# SparkFun_Qwiic_VR_IMU_Breakout_SchDoc.net
KiCad netlist of a schematic drawn in Altium Designer
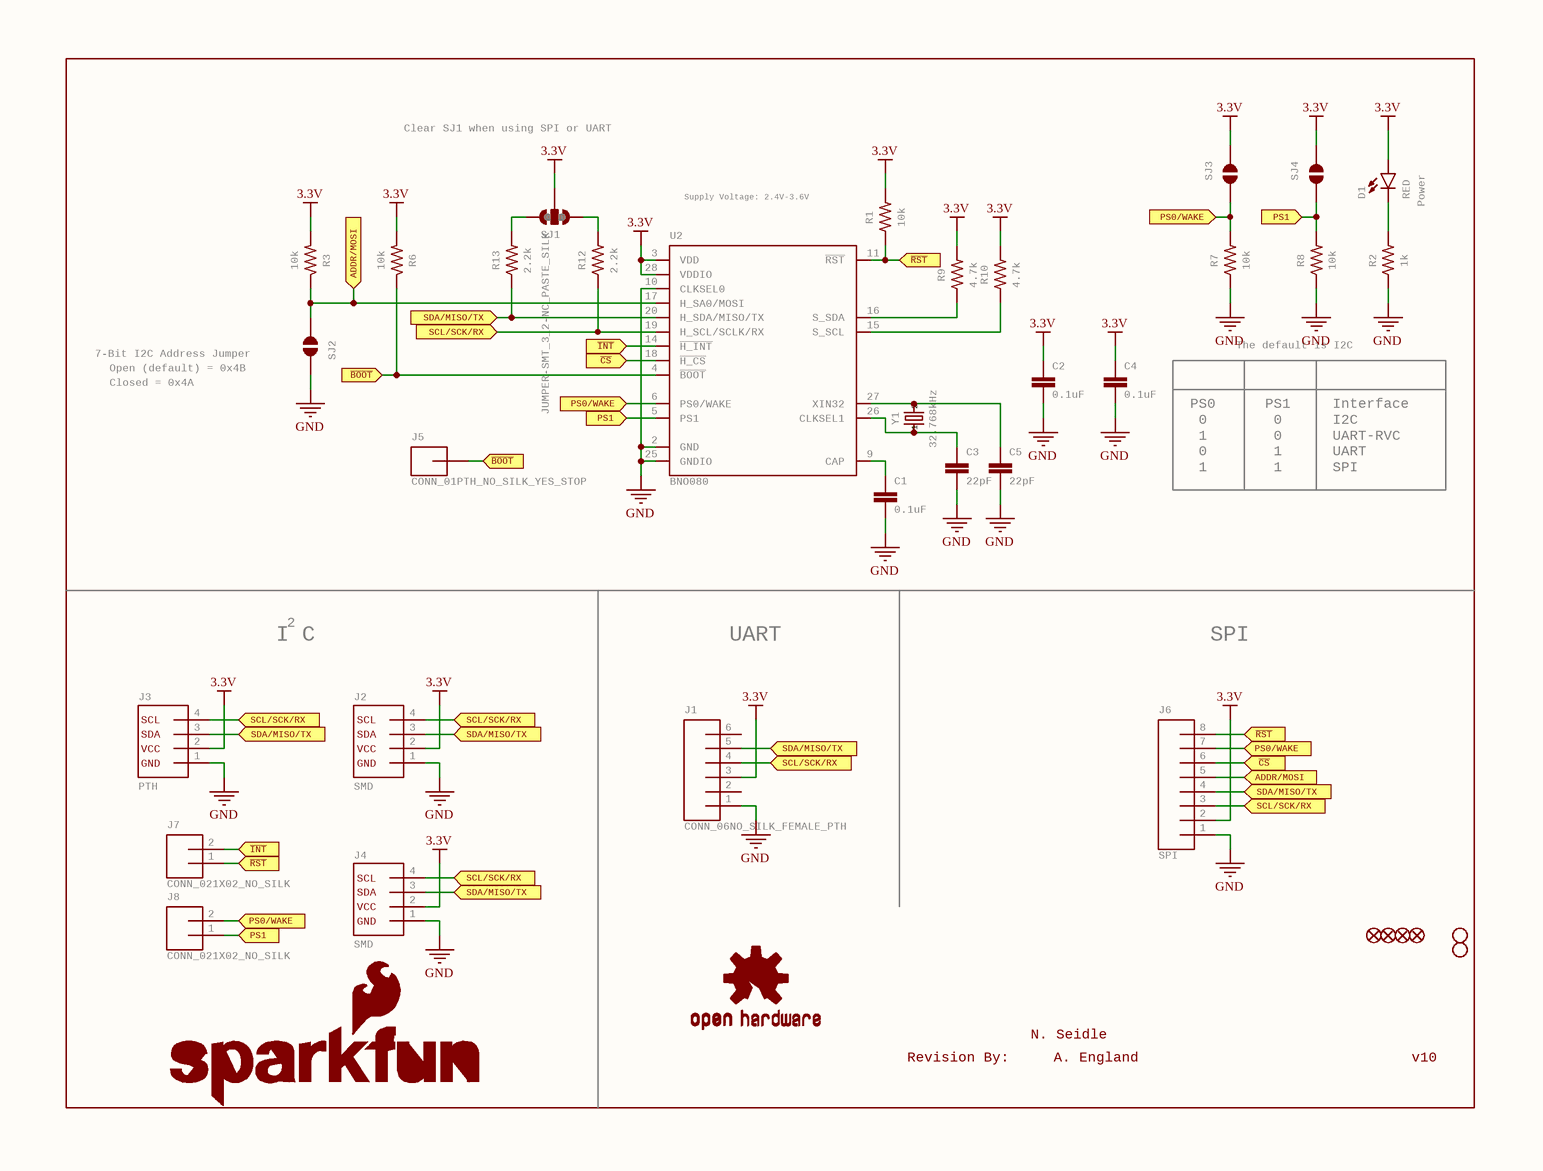
[diagram p0: SparkFun_Qwiic_VR_IMU_Breakout.SchDoc.SchDoc]

(export (version "E")
  (design (tool "Eeschema 10.0.6"))
  (components
    (comp (ref "C1")
      (value "0.1uF")
      (footprint "0603")
      (libsource (lib "SparkFun-Capacitors") (part "0.1UF-0603-25V-(+80/-20%)"))
    )
    (comp (ref "C2")
      (value "0.1uF")
      (footprint "0603")
      (libsource (lib "SparkFun-Capacitors") (part "0.1UF-0603-25V-(+80/-20%)"))
    )
    (comp (ref "C3")
      (value "22pF")
      (footprint "0603")
      (libsource (lib "SparkFun-Capacitors") (part "22PF-0603-50V-5%"))
    )
    (comp (ref "C4")
      (value "0.1uF")
      (footprint "0603")
      (libsource (lib "SparkFun-Capacitors") (part "0.1UF-0603-25V-(+80/-20%)"))
    )
    (comp (ref "C5")
      (value "22pF")
      (footprint "0603")
      (libsource (lib "SparkFun-Capacitors") (part "22PF-0603-50V-5%"))
    )
    (comp (ref "D1")
      (value "RED")
      (footprint "LED-0603")
      (libsource (lib "SparkFun-LED") (part "LED-RED0603"))
    )
    (comp (ref "J1")
      (value "CONN_06NO_SILK_FEMALE_PTH")
      (footprint "1X06_NO_SILK")
      (libsource (lib "SparkFun-Connectors") (part "CONN_06NO_SILK_FEMALE_PTH"))
    )
    (comp (ref "J2")
      (value "SMD")
      (footprint "1X04_1MM_RA")
      (fields
        (field (name "SDA") "SDA")
        (field (name "VCC") "VCC")
        (field (name "GND") "GND")
        (field (name "SCL") "SCL")
      )
      (libsource (lib "SparkX") (part "I2C_STANDARDJS-1MM"))
    )
    (comp (ref "J3")
      (value "PTH")
      (footprint "1X04_NO_SILK")
      (fields
        (field (name "SDA") "SDA")
        (field (name "VCC") "VCC")
        (field (name "GND") "GND")
        (field (name "SCL") "SCL")
      )
      (libsource (lib "SparkX") (part "I2C_STANDARD_NO_SILK"))
    )
    (comp (ref "J4")
      (value "SMD")
      (footprint "1X04_1MM_RA")
      (fields
        (field (name "SDA") "SDA")
        (field (name "VCC") "VCC")
        (field (name "GND") "GND")
        (field (name "SCL") "SCL")
      )
      (libsource (lib "SparkX") (part "I2C_STANDARDJS-1MM"))
    )
    (comp (ref "J5")
      (value "CONN_01PTH_NO_SILK_YES_STOP")
      (footprint "1X01_NO_SILK")
      (libsource (lib "SparkFun-Connectors") (part "CONN_01PTH_NO_SILK_YES_STOP"))
    )
    (comp (ref "J6")
      (value "SPI")
      (footprint "1X08_NO_SILK")
      (libsource (lib "SparkFun-Connectors") (part "CONN_08NO_SILK_FEMALE_PTH"))
    )
    (comp (ref "J7")
      (value "CONN_021X02_NO_SILK")
      (footprint "1X02_NO_SILK")
      (libsource (lib "SparkFun-Connectors") (part "CONN_021X02_NO_SILK"))
    )
    (comp (ref "J8")
      (value "CONN_021X02_NO_SILK")
      (footprint "1X02_NO_SILK")
      (libsource (lib "SparkFun-Connectors") (part "CONN_021X02_NO_SILK"))
    )
    (comp (ref "JP1")
      (value "FIDUCIALUFIDUCIAL")
      (footprint "MICRO-FIDUCIAL")
      (description "Fiducial Alignment PointsVarious fiducial points for machine vision alignment.")
      (libsource (lib "SparkFun") (part "FIDUCIALUFIDUCIAL"))
    )
    (comp (ref "JP2")
      (value "FIDUCIALUFIDUCIAL")
      (footprint "MICRO-FIDUCIAL")
      (description "Fiducial Alignment PointsVarious fiducial points for machine vision alignment.")
      (libsource (lib "SparkFun") (part "FIDUCIALUFIDUCIAL"))
    )
    (comp (ref "JP3")
      (value "STAND-OFF")
      (footprint "STAND-OFF")
      (libsource (lib "SparkFun") (part "STAND-OFF"))
    )
    (comp (ref "JP4")
      (value "STAND-OFF")
      (footprint "STAND-OFF")
      (libsource (lib "SparkFun") (part "STAND-OFF"))
    )
    (comp (ref "JP5")
      (value "FIDUCIALUFIDUCIAL")
      (footprint "MICRO-FIDUCIAL")
      (description "Fiducial Alignment PointsVarious fiducial points for machine vision alignment.")
      (libsource (lib "SparkFun") (part "FIDUCIALUFIDUCIAL"))
    )
    (comp (ref "JP6")
      (value "FIDUCIALUFIDUCIAL")
      (footprint "MICRO-FIDUCIAL")
      (description "Fiducial Alignment PointsVarious fiducial points for machine vision alignment.")
      (libsource (lib "SparkFun") (part "FIDUCIALUFIDUCIAL"))
    )
    (comp (ref "LOGO1")
      (value "OSHW-LOGOMINI")
      (footprint "OSHW-LOGO-MINI")
      (libsource (lib "SparkFun-Aesthetics") (part "OSHW-LOGOMINI"))
    )
    (comp (ref "LOGO2")
      (value "REVISION")
      (footprint "REVISION")
      (fields (field (name "REVISIONBY") "Revision By:"))
      (libsource (lib "SparkFun-Aesthetics") (part "REVISION"))
    )
    (comp (ref "LOGO4")
      (value "SFE_LOGO_FLAME.1_INCH")
      (footprint "SFE_LOGO_FLAME_.1")
      (libsource (lib "SparkFun-Aesthetics") (part "SFE_LOGO_FLAME.1_INCH"))
    )
    (comp (ref "LOGO5")
      (value "SFE_LOGO_NAME_FLAME.1_INCH")
      (footprint "SFE_LOGO_NAME_FLAME_.1")
      (libsource (lib "SparkFun-Aesthetics") (part "SFE_LOGO_NAME_FLAME.1_INCH"))
    )
    (comp (ref "R1")
      (value "10k")
      (footprint "0603")
      (libsource (lib "SparkFun-Resistors") (part "10KOHM-0603-1/10W-1%"))
    )
    (comp (ref "R2")
      (value "1k")
      (footprint "0603")
      (libsource (lib "SparkFun-Resistors") (part "1KOHM-0603-1/10W-1%"))
    )
    (comp (ref "R3")
      (value "10k")
      (footprint "0603")
      (libsource (lib "SparkFun-Resistors") (part "10KOHM-0603-1/10W-1%"))
    )
    (comp (ref "R6")
      (value "10k")
      (footprint "0603")
      (libsource (lib "SparkFun-Resistors") (part "10KOHM-0603-1/10W-1%"))
    )
    (comp (ref "R7")
      (value "10k")
      (footprint "0603")
      (libsource (lib "SparkFun-Resistors") (part "10KOHM-0603-1/10W-1%"))
    )
    (comp (ref "R8")
      (value "10k")
      (footprint "0603")
      (libsource (lib "SparkFun-Resistors") (part "10KOHM-0603-1/10W-1%"))
    )
    (comp (ref "R9")
      (value "4.7k")
      (footprint "0603")
      (libsource (lib "SparkFun-Resistors") (part "4.7KOHM-0603-1/10W-1%"))
    )
    (comp (ref "R10")
      (value "4.7k")
      (footprint "0603")
      (libsource (lib "SparkFun-Resistors") (part "4.7KOHM-0603-1/10W-1%"))
    )
    (comp (ref "R12")
      (value "2.2k")
      (footprint "0603")
      (libsource (lib "SparkFun-Resistors") (part "2.2KOHM-0603-1/10W-1%"))
    )
    (comp (ref "R13")
      (value "2.2k")
      (footprint "0603")
      (libsource (lib "SparkFun-Resistors") (part "2.2KOHM-0603-1/10W-1%"))
    )
    (comp (ref "SJ1")
      (value "JUMPER-SMT_3_2-NC_PASTE_SILK")
      (footprint "SMT-JUMPER_3_2-NC_PASTE_SILK")
      (libsource (lib "SparkFun-Jumpers") (part "JUMPER-SMT_3_2-NC_PASTE_SILK"))
    )
    (comp (ref "SJ2")
      (value "SOLDERJUMPERNO")
      (footprint "SJ_2S-NO")
      (libsource (lib "SparkFun") (part "SOLDERJUMPERNO"))
    )
    (comp (ref "SJ3")
      (value "SOLDERJUMPERNO")
      (footprint "SJ_2S-NO")
      (libsource (lib "SparkFun") (part "SOLDERJUMPERNO"))
    )
    (comp (ref "SJ4")
      (value "SOLDERJUMPERNO")
      (footprint "SJ_2S-NO")
      (libsource (lib "SparkFun") (part "SOLDERJUMPERNO"))
    )
    (comp (ref "U2")
      (value "BNO080")
      (footprint "LGA-28")
      (fields (field (name "LIBRARYNAME") "SparkFun-IC-Special-Function"))
      (libsource (lib "SparkFun-IC-Special-Function") (part "BNO080"))
    )
    (comp (ref "Y1")
      (value "32.768kHz")
      (footprint "CRYSTAL-SMD-3.2X1.5MM")
      (fields (field (name "1") "1") (field (name "2") "2") (field (name "LIBRARYNAME") "SparkFun-Clocks"))
      (libsource (lib "SparkFun-Clocks") (part "CRYSTAL-32.768KHZSMD-3.2X1.5"))
    )
  )
  (nets
    (net (code "1") (name "/ADDR{slash}MOSI") (class "Default")
      (node (ref "J6") (pin "5") (pinfunction "5_5") (pintype "passive"))
      (node (ref "R3") (pin "1") (pinfunction "1_1") (pintype "passive"))
      (node (ref "SJ2") (pin "2") (pinfunction "2_2") (pintype "passive"))
      (node (ref "U2") (pin "17") (pinfunction "H_SA0/MOSI_17") (pintype "bidirectional"))
    )
    (net (code "2") (name "/PS0{slash}WAKE") (class "Default")
      (node (ref "J6") (pin "7") (pinfunction "7_7") (pintype "passive"))
      (node (ref "J8") (pin "2") (pinfunction "2_2") (pintype "passive"))
      (node (ref "R7") (pin "2") (pinfunction "2_2") (pintype "passive"))
      (node (ref "SJ3") (pin "2") (pinfunction "2_2") (pintype "passive"))
      (node (ref "U2") (pin "6") (pinfunction "PS0/WAKE_6") (pintype "bidirectional"))
    )
    (net (code "3") (name "/PS1") (class "Default")
      (node (ref "J8") (pin "1") (pinfunction "1_1") (pintype "passive"))
      (node (ref "R8") (pin "2") (pinfunction "2_2") (pintype "passive"))
      (node (ref "SJ4") (pin "2") (pinfunction "2_2") (pintype "passive"))
      (node (ref "U2") (pin "5") (pinfunction "PS1_5") (pintype "bidirectional"))
    )
    (net (code "4") (name "/SCL{slash}SCK{slash}RX") (class "Default")
      (node (ref "J1") (pin "4") (pinfunction "4_4") (pintype "passive"))
      (node (ref "J2") (pin "4") (pinfunction "SCL_4") (pintype "passive"))
      (node (ref "J3") (pin "4") (pinfunction "SCL_4") (pintype "passive"))
      (node (ref "J4") (pin "4") (pinfunction "SCL_4") (pintype "passive"))
      (node (ref "J6") (pin "3") (pinfunction "3_3") (pintype "passive"))
      (node (ref "R12") (pin "1") (pinfunction "1_1") (pintype "passive"))
      (node (ref "U2") (pin "19") (pinfunction "H_SCL/SCLK/RX_19") (pintype "bidirectional"))
    )
    (net (code "5") (name "/SDA{slash}MISO{slash}TX") (class "Default")
      (node (ref "J1") (pin "5") (pinfunction "5_5") (pintype "passive"))
      (node (ref "J2") (pin "3") (pinfunction "SDA_3") (pintype "passive"))
      (node (ref "J3") (pin "3") (pinfunction "SDA_3") (pintype "passive"))
      (node (ref "J4") (pin "3") (pinfunction "SDA_3") (pintype "passive"))
      (node (ref "J6") (pin "4") (pinfunction "4_4") (pintype "passive"))
      (node (ref "R13") (pin "1") (pinfunction "1_1") (pintype "passive"))
      (node (ref "U2") (pin "20") (pinfunction "H_SDA/MISO/TX_20") (pintype "bidirectional"))
    )
    (net (code "6") (name "/~{BOOT}") (class "Default")
      (node (ref "J5") (pin "1") (pinfunction "1_1") (pintype "passive"))
      (node (ref "R6") (pin "1") (pinfunction "1_1") (pintype "passive"))
      (node (ref "U2") (pin "4") (pinfunction "~{BOOT}_4") (pintype "bidirectional"))
    )
    (net (code "7") (name "/~{CS}") (class "Default")
      (node (ref "J6") (pin "6") (pinfunction "6_6") (pintype "passive"))
      (node (ref "U2") (pin "18") (pinfunction "~{H_CS}_18") (pintype "bidirectional"))
    )
    (net (code "8") (name "/~{INT}") (class "Default")
      (node (ref "J7") (pin "2") (pinfunction "2_2") (pintype "passive"))
      (node (ref "U2") (pin "14") (pinfunction "~{H_INT}_14") (pintype "bidirectional"))
    )
    (net (code "9") (name "/~{RST}") (class "Default")
      (node (ref "J6") (pin "8") (pinfunction "8_8") (pintype "passive"))
      (node (ref "J7") (pin "1") (pinfunction "1_1") (pintype "passive"))
      (node (ref "R1") (pin "1") (pinfunction "1_1") (pintype "passive"))
      (node (ref "U2") (pin "11") (pinfunction "~{RST}_11") (pintype "bidirectional"))
    )
    (net (code "10") (name "3.3V") (class "Default")
      (node (ref "C2") (pin "1") (pinfunction "1_1") (pintype "passive"))
      (node (ref "C4") (pin "1") (pinfunction "1_1") (pintype "passive"))
      (node (ref "D1") (pin "A") (pinfunction "A_A") (pintype "passive"))
      (node (ref "J1") (pin "3") (pinfunction "3_3") (pintype "passive"))
      (node (ref "J2") (pin "2") (pinfunction "VCC_2") (pintype "power_in"))
      (node (ref "J3") (pin "2") (pinfunction "VCC_2") (pintype "power_in"))
      (node (ref "J4") (pin "2") (pinfunction "VCC_2") (pintype "power_in"))
      (node (ref "J6") (pin "2") (pinfunction "2_2") (pintype "passive"))
      (node (ref "R1") (pin "2") (pinfunction "2_2") (pintype "passive"))
      (node (ref "R10") (pin "2") (pinfunction "2_2") (pintype "passive"))
      (node (ref "R3") (pin "2") (pinfunction "2_2") (pintype "passive"))
      (node (ref "R6") (pin "2") (pinfunction "2_2") (pintype "passive"))
      (node (ref "R9") (pin "2") (pinfunction "2_2") (pintype "passive"))
      (node (ref "SJ1") (pin "2") (pinfunction "2_2") (pintype "passive"))
      (node (ref "SJ3") (pin "1") (pinfunction "1_1") (pintype "passive"))
      (node (ref "SJ4") (pin "1") (pinfunction "1_1") (pintype "passive"))
      (node (ref "U2") (pin "28") (pinfunction "VDDIO_28") (pintype "bidirectional"))
      (node (ref "U2") (pin "3") (pinfunction "VDD_3") (pintype "bidirectional"))
    )
    (net (code "11") (name "GND") (class "Default")
      (node (ref "C1") (pin "2") (pinfunction "2_2") (pintype "passive"))
      (node (ref "C2") (pin "2") (pinfunction "2_2") (pintype "passive"))
      (node (ref "C3") (pin "2") (pinfunction "2_2") (pintype "passive"))
      (node (ref "C4") (pin "2") (pinfunction "2_2") (pintype "passive"))
      (node (ref "C5") (pin "2") (pinfunction "2_2") (pintype "passive"))
      (node (ref "J1") (pin "1") (pinfunction "1_1") (pintype "passive"))
      (node (ref "J2") (pin "1") (pinfunction "GND_1") (pintype "power_in"))
      (node (ref "J3") (pin "1") (pinfunction "GND_1") (pintype "power_in"))
      (node (ref "J4") (pin "1") (pinfunction "GND_1") (pintype "power_in"))
      (node (ref "J6") (pin "1") (pinfunction "1_1") (pintype "passive"))
      (node (ref "R2") (pin "1") (pinfunction "1_1") (pintype "passive"))
      (node (ref "R7") (pin "1") (pinfunction "1_1") (pintype "passive"))
      (node (ref "R8") (pin "1") (pinfunction "1_1") (pintype "passive"))
      (node (ref "SJ2") (pin "1") (pinfunction "1_1") (pintype "passive"))
      (node (ref "U2") (pin "10") (pinfunction "CLKSEL0_10") (pintype "bidirectional"))
      (node (ref "U2") (pin "2") (pinfunction "GND_2") (pintype "bidirectional"))
      (node (ref "U2") (pin "25") (pinfunction "GNDIO_25") (pintype "bidirectional"))
    )
    (net (code "12") (name "Net-(D1-PadC)") (class "Default")
      (node (ref "D1") (pin "C") (pinfunction "C_C") (pintype "passive"))
      (node (ref "R2") (pin "2") (pinfunction "2_2") (pintype "passive"))
    )
    (net (code "13") (name "Net-(R12-Pad2)") (class "Default")
      (node (ref "R12") (pin "2") (pinfunction "2_2") (pintype "passive"))
      (node (ref "SJ1") (pin "1") (pinfunction "1_1") (pintype "passive"))
    )
    (net (code "14") (name "Net-(R13-Pad2)") (class "Default")
      (node (ref "R13") (pin "2") (pinfunction "2_2") (pintype "passive"))
      (node (ref "SJ1") (pin "3") (pinfunction "3_3") (pintype "passive"))
    )
    (net (code "15") (name "Net-(U2-CAP)") (class "Default")
      (node (ref "C1") (pin "1") (pinfunction "1_1") (pintype "passive"))
      (node (ref "U2") (pin "9") (pinfunction "CAP_9") (pintype "bidirectional"))
    )
    (net (code "16") (name "Net-(U2-CLKSEL1)") (class "Default")
      (node (ref "C3") (pin "1") (pinfunction "1_1") (pintype "passive"))
      (node (ref "U2") (pin "26") (pinfunction "CLKSEL1_26") (pintype "bidirectional"))
      (node (ref "Y1") (pin "P$1") (pinfunction "1_P$1") (pintype "passive"))
    )
    (net (code "17") (name "Net-(U2-S_SCL)") (class "Default")
      (node (ref "R10") (pin "1") (pinfunction "1_1") (pintype "passive"))
      (node (ref "U2") (pin "15") (pinfunction "S_SCL_15") (pintype "bidirectional"))
    )
    (net (code "18") (name "Net-(U2-S_SDA)") (class "Default")
      (node (ref "R9") (pin "1") (pinfunction "1_1") (pintype "passive"))
      (node (ref "U2") (pin "16") (pinfunction "S_SDA_16") (pintype "bidirectional"))
    )
    (net (code "19") (name "Net-(U2-XIN32)") (class "Default")
      (node (ref "C5") (pin "1") (pinfunction "1_1") (pintype "passive"))
      (node (ref "U2") (pin "27") (pinfunction "XIN32_27") (pintype "bidirectional"))
      (node (ref "Y1") (pin "P$2") (pinfunction "2_P$2") (pintype "passive"))
    )
    (net (code "20") (name "unconnected-(J1-Pad2)") (class "Default")
      (node (ref "J1") (pin "2") (pinfunction "2_2") (pintype "passive"))
    )
    (net (code "21") (name "unconnected-(J1-Pad6)") (class "Default")
      (node (ref "J1") (pin "6") (pinfunction "6_6") (pintype "passive"))
    )
  )
)
